# YakupTrkn1.net
KiCad netlist of a schematic drawn in Altium Designer
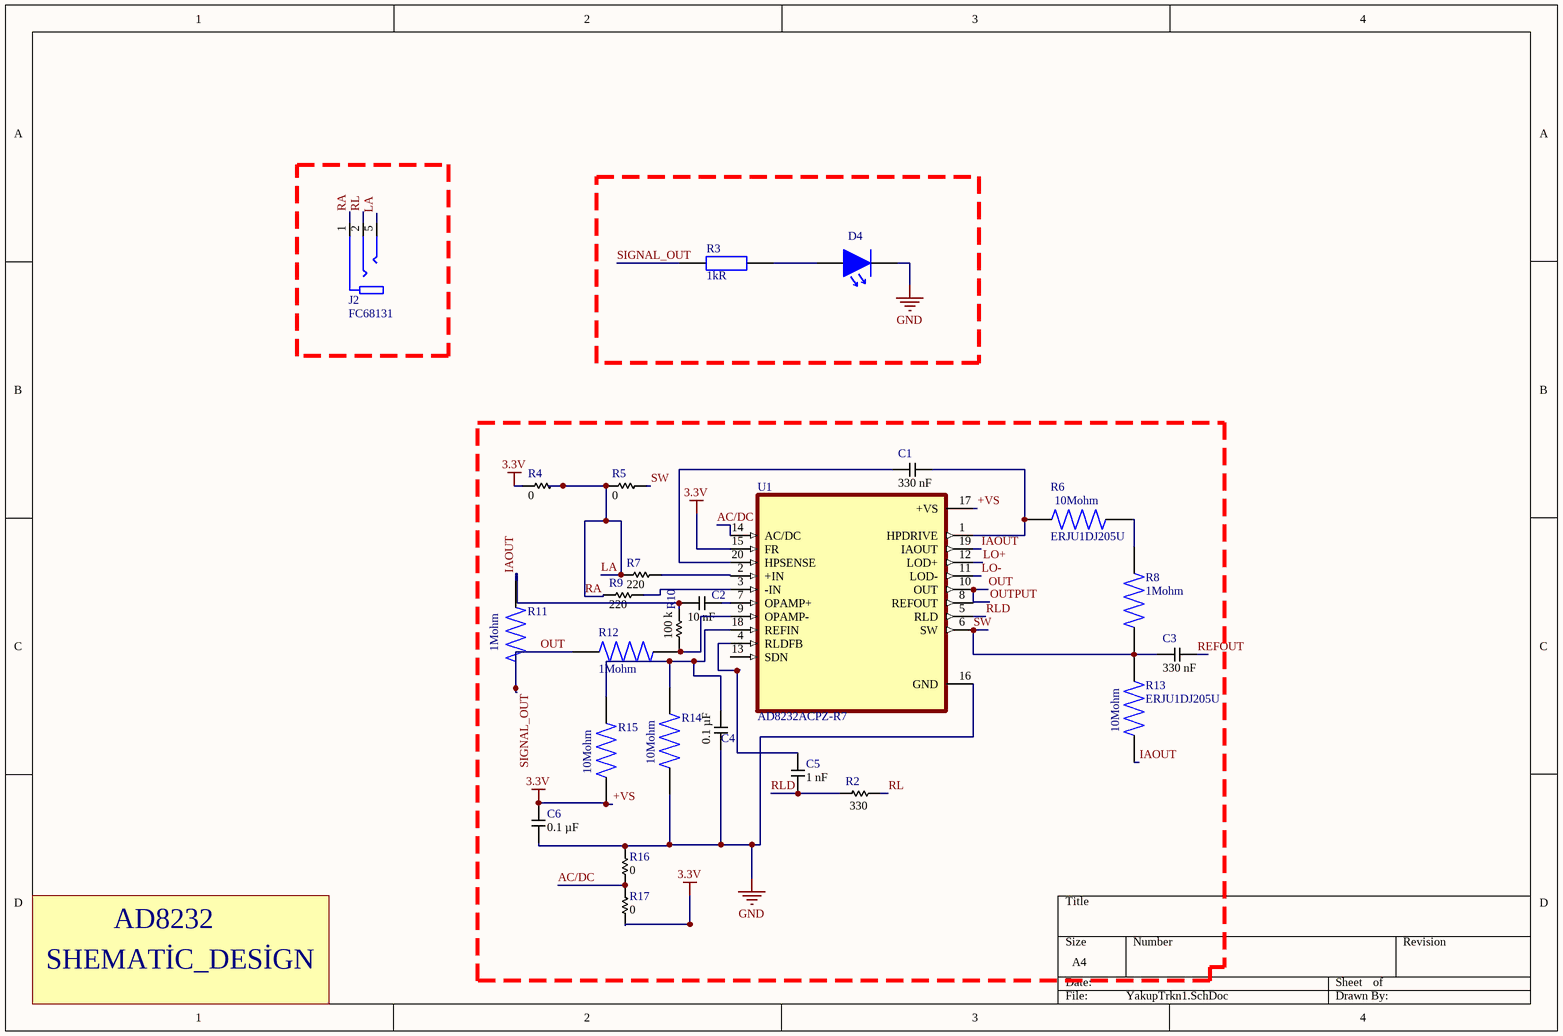
[diagram p0: YakupTrkn1.SchDoc]

(export (version "E")
  (design (tool "Eeschema 10.0.6"))
  (components
    (comp (ref "C1")
      (value "CL21B334KOCNNNC")
      (footprint "SAMSUNG_CAP_0805_095")
      (description "CAP CER 0.33UF 16V X7R 0805")
      (fields (field (name "CAPACITANCE") "330 nF"))
      (libsource (lib "YakupTrkn") (part "CL21B334KOCNNNC"))
    )
    (comp (ref "C2")
      (value "CL10B103KB8NNNL")
      (footprint "SAMSUNG_CAP_0603_090")
      (description "CAP CER 10000PF 50V X7R 0603")
      (fields (field (name "CAPACITANCE") "10 nF"))
      (libsource (lib "YakupTrkn") (part "CL10B103KB8NNNL"))
    )
    (comp (ref "C3")
      (value "CL21B334KOCNNNC")
      (footprint "SAMSUNG_CAP_0805_095")
      (description "CAP CER 0.33UF 16V X7R 0805")
      (fields (field (name "CAPACITANCE") "330 nF"))
      (libsource (lib "YakupTrkn") (part "CL21B334KOCNNNC"))
    )
    (comp (ref "C4")
      (value "CL21B104MACNNNC")
      (footprint "SAMSUNG_CAP_0805_095")
      (description "CAP CER 0.1UF 25V X7R 0805")
      (fields (field (name "CAPACITANCE") "0.1 µF"))
      (libsource (lib "YakupTrkn") (part "CL21B104MACNNNC"))
    )
    (comp (ref "C5")
      (value "CL21B102KBCNNNC")
      (footprint "SAMSUNG_CAP_0805_095")
      (description "CAP CER 1000PF 50V X7R 0805")
      (fields (field (name "CAPACITANCE") "1 nF"))
      (libsource (lib "YakupTrkn") (part "CL21B102KBCNNNC"))
    )
    (comp (ref "C6")
      (value "CL21B104MACNNNC")
      (footprint "SAMSUNG_CAP_0805_095")
      (description "CAP CER 0.1UF 25V X7R 0805")
      (fields (field (name "CAPACITANCE") "0.1 µF"))
      (libsource (lib "YakupTrkn") (part "CL21B104MACNNNC"))
    )
    (comp (ref "D4")
      (value "LH R974-LP-1")
      (footprint "LED_RED_0805")
      (description "LED Uni-Color Hyper Red 660nm 2-Pin Chip 0805(2012Metric) T/R")
      (fields (field (name "MANUFACTURER") "Osram Opto") (field (name "DESIGNED BY") "BERK"))
      (libsource (lib "YakupTrkn") (part "LED RED 0805"))
    )
    (comp (ref "J2")
      (value "FC68131")
      (footprint "FC68131:CLIFF_FC68131")
      (description "Stereo Jack, 3.5mm, 3pos, Pcb")
      (fields (field (name "MF") "{'manufacturer': u'Cliff'}"))
      (libsource (lib "YakupTrkn") (part "FC68131"))
    )
    (comp (ref "R2")
      (value "0805S8J0331T5E")
      (footprint "ROYALOHM_RES_0805")
      (description "RES SMD 330R OHM 5% 1/8W 0805")
      (fields (field (name "RESISTANCE") "330"))
      (libsource (lib "YakupTrkn") (part "0805S8J0331T5E"))
    )
    (comp (ref "R3")
      (value "RC0603FR-0710KL")
      (footprint "RES_0603")
      (description "RES 1K %1 OHM 0603 SMD")
      (fields
        (field (name "MANUFACTURER") "Yageo")
        (field (name "MANUFACTURER PART NUMBER") "RC0603JR-071KL")
        (field (name "RESISTANCE") "1kR")
        (field (name "DESIGNED BY") "BERK")
      )
      (libsource (lib "YakupTrkn") (part "RES 1K OHM 0603"))
    )
    (comp (ref "R4")
      (value "0603SAJ0000TDE")
      (footprint "ROYALOHM_RES_0603")
      (description "RES SMD 0 OHM 5% 1/10W 0603")
      (fields (field (name "RESISTANCE") "0"))
      (libsource (lib "YakupTrkn") (part "0603SAJ0000TDE"))
    )
    (comp (ref "R5")
      (value "0603SAJ0000TDE")
      (footprint "ROYALOHM_RES_0603")
      (description "RES SMD 0 OHM 5% 1/10W 0603")
      (fields (field (name "RESISTANCE") "0"))
      (libsource (lib "YakupTrkn") (part "0603SAJ0000TDE"))
    )
    (comp (ref "R6")
      (value "ERJU1DJ205U")
      (footprint "ERJ-U1DJ205U:RES_ERJU1DJ205U")
      (fields (field (name "MF") "{'manufacturer': u'Panasonic'}"))
      (libsource (lib "YakupTrkn") (part "ERJU1DJ205U"))
    )
    (comp (ref "R7")
      (value "0603SAJ0221T5E")
      (footprint "ROYALOHM_RES_0603")
      (description "RES SMD 220R OHM 5% 1/10W 0603")
      (fields (field (name "RESISTANCE") "220"))
      (libsource (lib "YakupTrkn") (part "0603SAJ0221T5E"))
    )
    (comp (ref "R8")
      (value "1Mohm")
      (footprint "RNCS0805BKE1M00:RESC2012X65N")
      (fields
        (field (name "MP") "RNCS0805BKE1M00")
        (field (name "MF") "{'manufacturer': u'Stackpole Electronics Inc'}")
      )
      (libsource (lib "YakupTrkn") (part "RNCS0805BKE1M00"))
    )
    (comp (ref "R9")
      (value "0603SAJ0221T5E")
      (footprint "ROYALOHM_RES_0603")
      (description "RES SMD 220R OHM 5% 1/10W 0603")
      (fields (field (name "RESISTANCE") "220"))
      (libsource (lib "YakupTrkn") (part "0603SAJ0221T5E"))
    )
    (comp (ref "R10")
      (value "0805S8J0104T5E")
      (footprint "ROYALOHM_RES_0805")
      (description "RES SMD 100K OHM 5% 1/8W 0805")
      (fields (field (name "RESISTANCE") "100 k"))
      (libsource (lib "YakupTrkn") (part "0805S8J0104T5E"))
    )
    (comp (ref "R11")
      (value "1Mohm")
      (footprint "RNCS0805BKE1M00:RESC2012X65N")
      (fields
        (field (name "MP") "RNCS0805BKE1M00")
        (field (name "MF") "{'manufacturer': u'Stackpole Electronics Inc'}")
      )
      (libsource (lib "YakupTrkn") (part "RNCS0805BKE1M00"))
    )
    (comp (ref "R12")
      (value "1Mohm")
      (footprint "RNCS0805BKE1M00:RESC2012X65N")
      (fields
        (field (name "MP") "RNCS0805BKE1M00")
        (field (name "MF") "{'manufacturer': u'Stackpole Electronics Inc'}")
      )
      (libsource (lib "YakupTrkn") (part "RNCS0805BKE1M00"))
    )
    (comp (ref "R13")
      (value "ERJU1DJ205U")
      (footprint "ERJ-U1DJ205U:RES_ERJU1DJ205U")
      (fields (field (name "MF") "{'manufacturer': u'Panasonic'}"))
      (libsource (lib "YakupTrkn") (part "ERJU1DJ205U"))
    )
    (comp (ref "R14")
      (value "~")
      (footprint "ERJ-U1DJ205U:RES_ERJU1DJ205U")
      (fields (field (name "MF") "{'manufacturer': u'Panasonic'}") (field (name "MP") "ERJU1DJ205U"))
      (libsource (lib "YakupTrkn") (part "ERJU1DJ205U"))
    )
    (comp (ref "R15")
      (value "~")
      (footprint "ERJ-U1DJ205U:RES_ERJU1DJ205U")
      (fields (field (name "MF") "{'manufacturer': u'Panasonic'}") (field (name "MP") "ERJU1DJ205U"))
      (libsource (lib "YakupTrkn") (part "ERJU1DJ205U"))
    )
    (comp (ref "R16")
      (value "0603SAJ0000TDE")
      (footprint "ROYALOHM_RES_0603")
      (description "RES SMD 0 OHM 5% 1/10W 0603")
      (fields (field (name "RESISTANCE") "0"))
      (libsource (lib "YakupTrkn") (part "0603SAJ0000TDE"))
    )
    (comp (ref "R17")
      (value "0603SAJ0000TDE")
      (footprint "ROYALOHM_RES_0603")
      (description "RES SMD 0 OHM 5% 1/10W 0603")
      (fields (field (name "RESISTANCE") "0"))
      (libsource (lib "YakupTrkn") (part "0603SAJ0000TDE"))
    )
    (comp (ref "U1")
      (value "AD8232ACPZ-R7")
      (footprint "AD8232ACPZ-R7:QFN50P400X400X100-21N")
      (fields (field (name "MF") "{'manufacturer': u'Analog Devices'}"))
      (libsource (lib "YakupTrkn") (part "AD8232ACPZ-R7"))
    )
  )
  (nets
    (net (code "1") (name "/AC{slash}DC") (class "Default")
      (node (ref "R16") (pin "1") (pinfunction "1_1") (pintype "passive"))
      (node (ref "R17") (pin "2") (pinfunction "2_2") (pintype "passive"))
      (node (ref "U1") (pin "14") (pinfunction "AC/DC_14") (pintype "input"))
    )
    (net (code "2") (name "/IAOUT") (class "Default")
      (node (ref "C2") (pin "1") (pinfunction "1_1") (pintype "passive"))
      (node (ref "R10") (pin "1") (pinfunction "1_1") (pintype "passive"))
      (node (ref "R11") (pin "1") (pinfunction "1_1") (pintype "passive"))
      (node (ref "R13") (pin "1") (pinfunction "1_1") (pintype "passive"))
      (node (ref "U1") (pin "19") (pinfunction "IAOUT_19") (pintype "output"))
    )
    (net (code "3") (name "/LA") (class "Default")
      (node (ref "J2") (pin "1") (pinfunction "SLEEVE_1") (pintype "passive"))
      (node (ref "J2") (pin "5") (pinfunction "TIP_5") (pintype "passive"))
      (node (ref "R4") (pin "2") (pinfunction "2_2") (pintype "passive"))
      (node (ref "R5") (pin "1") (pinfunction "1_1") (pintype "passive"))
      (node (ref "R7") (pin "1") (pinfunction "1_1") (pintype "passive"))
      (node (ref "R9") (pin "1") (pinfunction "1_1") (pintype "passive"))
    )
    (net (code "4") (name "/LO+") (class "Default")
      (node (ref "U1") (pin "12") (pinfunction "LOD+_12") (pintype "output"))
    )
    (net (code "5") (name "/LO-") (class "Default")
      (node (ref "U1") (pin "11") (pinfunction "LOD-_11") (pintype "output"))
    )
    (net (code "6") (name "/OUT") (class "Default")
      (node (ref "R11") (pin "2") (pinfunction "2_2") (pintype "passive"))
      (node (ref "R12") (pin "2") (pinfunction "2_2") (pintype "passive"))
      (node (ref "R3") (pin "1") (pinfunction "1_1") (pintype "passive"))
      (node (ref "U1") (pin "10") (pinfunction "OUT_10") (pintype "output"))
    )
    (net (code "7") (name "/REFOUT") (class "Default")
      (node (ref "C3") (pin "2") (pinfunction "2_2") (pintype "passive"))
    )
    (net (code "8") (name "/RL") (class "Default")
      (node (ref "J2") (pin "2") (pinfunction "RING_2") (pintype "passive"))
      (node (ref "R2") (pin "2") (pinfunction "2_2") (pintype "passive"))
    )
    (net (code "9") (name "/RLD") (class "Default")
      (node (ref "C5") (pin "1") (pinfunction "1_1") (pintype "passive"))
      (node (ref "R2") (pin "1") (pinfunction "1_1") (pintype "passive"))
      (node (ref "U1") (pin "5") (pinfunction "RLD_5") (pintype "output"))
    )
    (net (code "10") (name "/SW") (class "Default")
      (node (ref "C3") (pin "1") (pinfunction "1_1") (pintype "passive"))
      (node (ref "R13") (pin "2") (pinfunction "2_2") (pintype "passive"))
      (node (ref "R5") (pin "2") (pinfunction "2_2") (pintype "passive"))
      (node (ref "R8") (pin "2") (pinfunction "2_2") (pintype "passive"))
      (node (ref "U1") (pin "6") (pinfunction "SW_6") (pintype "output"))
    )
    (net (code "11") (name "3.3V") (class "Default")
      (node (ref "C6") (pin "2") (pinfunction "2_2") (pintype "passive"))
      (node (ref "R15") (pin "1") (pinfunction "1_1") (pintype "passive"))
      (node (ref "R17") (pin "1") (pinfunction "1_1") (pintype "passive"))
      (node (ref "R4") (pin "1") (pinfunction "1_1") (pintype "passive"))
      (node (ref "U1") (pin "15") (pinfunction "FR_15") (pintype "input"))
      (node (ref "U1") (pin "17") (pinfunction "+VS_17") (pintype "power_in"))
    )
    (net (code "12") (name "GND") (class "Default")
      (node (ref "C4") (pin "2") (pinfunction "2_2") (pintype "passive"))
      (node (ref "C6") (pin "1") (pinfunction "1_1") (pintype "passive"))
      (node (ref "D4") (pin "1") (pinfunction "1_1") (pintype "power_in"))
      (node (ref "R14") (pin "1") (pinfunction "1_1") (pintype "passive"))
      (node (ref "R16") (pin "2") (pinfunction "2_2") (pintype "passive"))
      (node (ref "U1") (pin "16") (pinfunction "GND_16") (pintype "power_in"))
    )
    (net (code "13") (name "Net-(D4-Pad2)") (class "Default")
      (node (ref "D4") (pin "2") (pinfunction "2_2") (pintype "power_in"))
      (node (ref "R3") (pin "2") (pinfunction "2_2") (pintype "passive"))
    )
    (net (code "14") (name "Net-(R6-Pad2)") (class "Default")
      (node (ref "R6") (pin "2") (pinfunction "2_2") (pintype "passive"))
      (node (ref "R8") (pin "1") (pinfunction "1_1") (pintype "passive"))
    )
    (net (code "15") (name "Net-(U1-+IN)") (class "Default")
      (node (ref "R7") (pin "2") (pinfunction "2_2") (pintype "passive"))
      (node (ref "U1") (pin "2") (pinfunction "+IN_2") (pintype "input"))
    )
    (net (code "16") (name "Net-(U1--IN)") (class "Default")
      (node (ref "R9") (pin "2") (pinfunction "2_2") (pintype "passive"))
      (node (ref "U1") (pin "3") (pinfunction "-IN_3") (pintype "input"))
    )
    (net (code "17") (name "Net-(U1-HPDRIVE)") (class "Default")
      (node (ref "C1") (pin "2") (pinfunction "2_2") (pintype "passive"))
      (node (ref "R6") (pin "1") (pinfunction "1_1") (pintype "passive"))
      (node (ref "U1") (pin "1") (pinfunction "HPDRIVE_1") (pintype "output"))
    )
    (net (code "18") (name "Net-(U1-HPSENSE)") (class "Default")
      (node (ref "C1") (pin "1") (pinfunction "1_1") (pintype "passive"))
      (node (ref "U1") (pin "20") (pinfunction "HPSENSE_20") (pintype "input"))
    )
    (net (code "19") (name "Net-(U1-OPAMP+)") (class "Default")
      (node (ref "C2") (pin "2") (pinfunction "2_2") (pintype "passive"))
      (node (ref "U1") (pin "7") (pinfunction "OPAMP+_7") (pintype "input"))
    )
    (net (code "20") (name "Net-(U1-OPAMP-)") (class "Default")
      (node (ref "R10") (pin "2") (pinfunction "2_2") (pintype "passive"))
      (node (ref "R12") (pin "1") (pinfunction "1_1") (pintype "passive"))
      (node (ref "U1") (pin "9") (pinfunction "OPAMP-_9") (pintype "input"))
    )
    (net (code "21") (name "Net-(U1-REFIN)") (class "Default")
      (node (ref "C4") (pin "1") (pinfunction "1_1") (pintype "passive"))
      (node (ref "R14") (pin "2") (pinfunction "2_2") (pintype "passive"))
      (node (ref "R15") (pin "2") (pinfunction "2_2") (pintype "passive"))
      (node (ref "U1") (pin "18") (pinfunction "REFIN_18") (pintype "input"))
    )
    (net (code "22") (name "Net-(U1-RLDFB)") (class "Default")
      (node (ref "C5") (pin "2") (pinfunction "2_2") (pintype "passive"))
      (node (ref "U1") (pin "4") (pinfunction "RLDFB_4") (pintype "input"))
    )
    (net (code "23") (name "unconnected-(U1-REFOUT-Pad8)") (class "Default")
      (node (ref "U1") (pin "8") (pinfunction "REFOUT_8") (pintype "output"))
    )
    (net (code "24") (name "unconnected-(U1-SDN-Pad13)") (class "Default")
      (node (ref "U1") (pin "13") (pinfunction "SDN_13") (pintype "input"))
    )
  )
)
